# CAN_shield_rev0.net
KiCad netlist of a schematic drawn in EAGLE
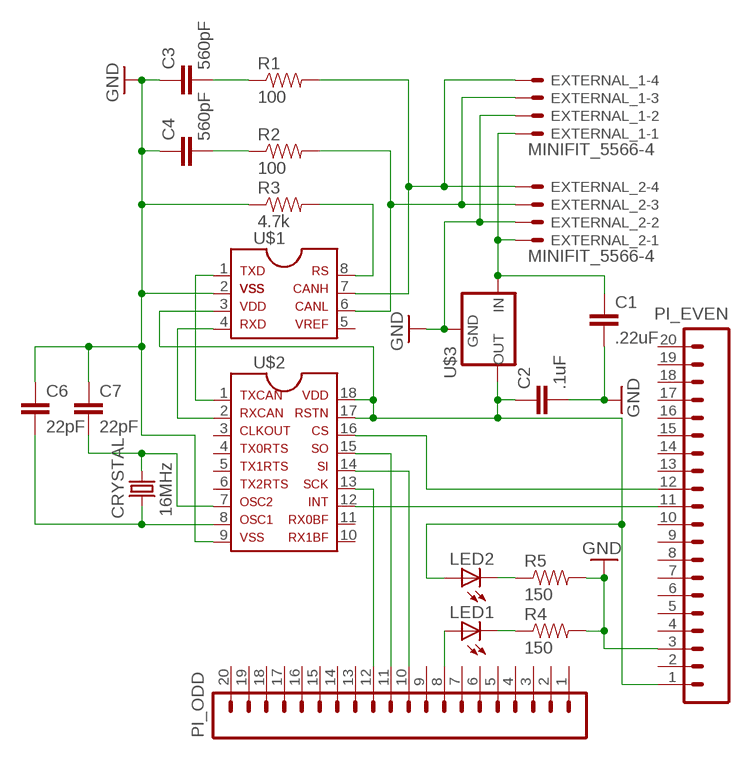
[diagram p0: schematic, sheet 1]

(export (version "E")
  (design (tool "Eeschema 10.0.6"))
  (components
    (comp (ref "C1")
      (value ".22uF")
      (footprint "eagle-import:0805")
      (libsource (lib "eagle-import") (part "CAP0805"))
    )
    (comp (ref "C2")
      (value ".1uF")
      (footprint "eagle-import:0805")
      (libsource (lib "eagle-import") (part "CAP0805"))
    )
    (comp (ref "C3")
      (value "560pF")
      (footprint "eagle-import:0805")
      (libsource (lib "eagle-import") (part "CAP0805"))
    )
    (comp (ref "C4")
      (value "560pF")
      (footprint "eagle-import:0805")
      (libsource (lib "eagle-import") (part "CAP0805"))
    )
    (comp (ref "C6")
      (value "22pF")
      (footprint "eagle-import:0805")
      (libsource (lib "eagle-import") (part "CAP0805"))
    )
    (comp (ref "C7")
      (value "22pF")
      (footprint "eagle-import:0805")
      (libsource (lib "eagle-import") (part "CAP0805"))
    )
    (comp (ref "CRYSTAL")
      (value "16MHz")
      (footprint "eagle-import:HC49UP")
      (libsource (lib "eagle-import") (part "CRYSTALSMD"))
    )
    (comp (ref "EXTERNAL_1")
      (value "MINIFIT_5566-4")
      (footprint "eagle-import:MINIFIT_5566-4")
      (libsource (lib "eagle-import") (part "MINIFIT_5566-4"))
    )
    (comp (ref "EXTERNAL_2")
      (value "MINIFIT_5566-4")
      (footprint "eagle-import:MINIFIT_5566-4")
      (libsource (lib "eagle-import") (part "MINIFIT_5566-4"))
    )
    (comp (ref "LED1")
      (value "LED-0805")
      (footprint "eagle-import:LED-805")
      (libsource (lib "eagle-import") (part "LED-0805"))
    )
    (comp (ref "LED2")
      (value "LED-0805")
      (footprint "eagle-import:LED-805")
      (libsource (lib "eagle-import") (part "LED-0805"))
    )
    (comp (ref "PI_EVEN")
      (value "M20")
      (footprint "eagle-import:1X20")
      (libsource (lib "eagle-import") (part "M20"))
    )
    (comp (ref "PI_ODD")
      (value "M20")
      (footprint "eagle-import:1X20")
      (libsource (lib "eagle-import") (part "M20"))
    )
    (comp (ref "R1")
      (value "100")
      (footprint "eagle-import:0805")
      (libsource (lib "eagle-import") (part "RESISTOR0805-RES"))
    )
    (comp (ref "R2")
      (value "100")
      (footprint "eagle-import:0805")
      (libsource (lib "eagle-import") (part "RESISTOR0805-RES"))
    )
    (comp (ref "R3")
      (value "4.7k")
      (footprint "eagle-import:0805")
      (libsource (lib "eagle-import") (part "RESISTOR0805-RES"))
    )
    (comp (ref "R4")
      (value "150")
      (footprint "eagle-import:0805")
      (libsource (lib "eagle-import") (part "RESISTOR0805-RES"))
    )
    (comp (ref "R5")
      (value "150")
      (footprint "eagle-import:0805")
      (libsource (lib "eagle-import") (part "RESISTOR0805-RES"))
    )
    (comp (ref "U$1")
      (value "MCP2551")
      (footprint "eagle-import:SOIC-08")
      (libsource (lib "eagle-import") (part "MCP2551"))
    )
    (comp (ref "U$2")
      (value "MCP2515SMD")
      (footprint "eagle-import:SOIC-18W")
      (libsource (lib "eagle-import") (part "MCP2515SMD"))
    )
    (comp (ref "U$3")
      (value "5V_REGULATOR_LM340-NLM340MPX-5.0/NOPB")
      (footprint "eagle-import:SOT223")
      (libsource (lib "eagle-import") (part "5V_REGULATOR_LM340-NLM340MPX-5.0/NOPB"))
    )
  )
  (nets
    (net (code "1") (name "GND") (class "Default")
      (node (ref "C1") (pin "2") (pinfunction "2_2") (pintype "passive"))
      (node (ref "C2") (pin "2") (pinfunction "2_2") (pintype "passive"))
      (node (ref "C3") (pin "1") (pinfunction "1_1") (pintype "passive"))
      (node (ref "C4") (pin "1") (pinfunction "1_1") (pintype "passive"))
      (node (ref "C6") (pin "1") (pinfunction "1_1") (pintype "passive"))
      (node (ref "C7") (pin "1") (pinfunction "1_1") (pintype "passive"))
      (node (ref "EXTERNAL_1") (pin "2") (pinfunction "S_2") (pintype "passive"))
      (node (ref "EXTERNAL_2") (pin "2") (pinfunction "S_2") (pintype "passive"))
      (node (ref "PI_EVEN") (pin "3") (pinfunction "3_3") (pintype "passive"))
      (node (ref "R3") (pin "1") (pinfunction "1_1") (pintype "passive"))
      (node (ref "R4") (pin "2") (pinfunction "2_2") (pintype "passive"))
      (node (ref "R5") (pin "2") (pinfunction "2_2") (pintype "passive"))
      (node (ref "U$1") (pin "2") (pinfunction "2_2") (pintype "passive"))
      (node (ref "U$2") (pin "9") (pinfunction "9_9") (pintype "passive"))
      (node (ref "U$3") (pin "2") (pinfunction "GND_2") (pintype "input"))
      (node (ref "U$3") (pin "4") (pinfunction "GND_4") (pintype "input"))
    )
    (net (code "2") (name "Net-(C3-Pad2)") (class "Default")
      (node (ref "C3") (pin "2") (pinfunction "2_2") (pintype "passive"))
      (node (ref "R1") (pin "1") (pinfunction "1_1") (pintype "passive"))
    )
    (net (code "3") (name "Net-(C4-Pad2)") (class "Default")
      (node (ref "C4") (pin "2") (pinfunction "2_2") (pintype "passive"))
      (node (ref "R2") (pin "1") (pinfunction "1_1") (pintype "passive"))
    )
    (net (code "4") (name "Net-(C6-Pad2)") (class "Default")
      (node (ref "C6") (pin "2") (pinfunction "2_2") (pintype "passive"))
      (node (ref "CRYSTAL") (pin "2") (pinfunction "2_2") (pintype "passive"))
      (node (ref "U$2") (pin "8") (pinfunction "8_8") (pintype "passive"))
    )
    (net (code "5") (name "Net-(C7-Pad2)") (class "Default")
      (node (ref "C7") (pin "2") (pinfunction "2_2") (pintype "passive"))
      (node (ref "CRYSTAL") (pin "1") (pinfunction "1_1") (pintype "passive"))
      (node (ref "U$2") (pin "7") (pinfunction "7_7") (pintype "passive"))
    )
    (net (code "6") (name "Net-(EXTERNAL_1A-S)") (class "Default")
      (node (ref "C1") (pin "1") (pinfunction "1_1") (pintype "passive"))
      (node (ref "EXTERNAL_1") (pin "1") (pinfunction "S_1") (pintype "passive"))
      (node (ref "EXTERNAL_2") (pin "1") (pinfunction "S_1") (pintype "passive"))
      (node (ref "U$3") (pin "1") (pinfunction "IN_1") (pintype "input"))
    )
    (net (code "7") (name "Net-(EXTERNAL_1C-S)") (class "Default")
      (node (ref "EXTERNAL_1") (pin "3") (pinfunction "S_3") (pintype "passive"))
      (node (ref "EXTERNAL_2") (pin "3") (pinfunction "S_3") (pintype "passive"))
      (node (ref "R2") (pin "2") (pinfunction "2_2") (pintype "passive"))
      (node (ref "U$1") (pin "6") (pinfunction "6_6") (pintype "passive"))
    )
    (net (code "8") (name "Net-(EXTERNAL_1D-S)") (class "Default")
      (node (ref "EXTERNAL_1") (pin "4") (pinfunction "S_4") (pintype "passive"))
      (node (ref "EXTERNAL_2") (pin "4") (pinfunction "S_4") (pintype "passive"))
      (node (ref "R1") (pin "2") (pinfunction "2_2") (pintype "passive"))
      (node (ref "U$1") (pin "7") (pinfunction "7_7") (pintype "passive"))
    )
    (net (code "9") (name "Net-(LED1-PadA)") (class "Default")
      (node (ref "LED1") (pin "A") (pinfunction "A_A") (pintype "passive"))
      (node (ref "PI_ODD") (pin "8") (pinfunction "8_8") (pintype "passive"))
    )
    (net (code "10") (name "Net-(LED1-PadC)") (class "Default")
      (node (ref "LED1") (pin "C") (pinfunction "C_C") (pintype "passive"))
      (node (ref "R4") (pin "1") (pinfunction "1_1") (pintype "passive"))
    )
    (net (code "11") (name "Net-(LED2-PadC)") (class "Default")
      (node (ref "LED2") (pin "C") (pinfunction "C_C") (pintype "passive"))
      (node (ref "R5") (pin "1") (pinfunction "1_1") (pintype "passive"))
    )
    (net (code "12") (name "Net-(PI_EVEN-Pad11)") (class "Default")
      (node (ref "PI_EVEN") (pin "11") (pinfunction "11_11") (pintype "passive"))
      (node (ref "U$2") (pin "12") (pinfunction "12_12") (pintype "passive"))
    )
    (net (code "13") (name "Net-(PI_EVEN-Pad12)") (class "Default")
      (node (ref "PI_EVEN") (pin "12") (pinfunction "12_12") (pintype "passive"))
      (node (ref "U$2") (pin "16") (pinfunction "16_16") (pintype "passive"))
    )
    (net (code "14") (name "Net-(PI_ODD-Pad10)") (class "Default")
      (node (ref "PI_ODD") (pin "10") (pinfunction "10_10") (pintype "passive"))
      (node (ref "U$2") (pin "14") (pinfunction "14_14") (pintype "passive"))
    )
    (net (code "15") (name "Net-(PI_ODD-Pad11)") (class "Default")
      (node (ref "PI_ODD") (pin "11") (pinfunction "11_11") (pintype "passive"))
      (node (ref "U$2") (pin "15") (pinfunction "15_15") (pintype "passive"))
    )
    (net (code "16") (name "Net-(PI_ODD-Pad12)") (class "Default")
      (node (ref "PI_ODD") (pin "12") (pinfunction "12_12") (pintype "passive"))
      (node (ref "U$2") (pin "13") (pinfunction "13_13") (pintype "passive"))
    )
    (net (code "17") (name "Net-(R3-Pad2)") (class "Default")
      (node (ref "R3") (pin "2") (pinfunction "2_2") (pintype "passive"))
      (node (ref "U$1") (pin "8") (pinfunction "8_8") (pintype "passive"))
    )
    (net (code "18") (name "Net-(U$1-Pad1)") (class "Default")
      (node (ref "U$1") (pin "1") (pinfunction "1_1") (pintype "passive"))
      (node (ref "U$2") (pin "1") (pinfunction "1_1") (pintype "passive"))
    )
    (net (code "19") (name "Net-(U$1-Pad4)") (class "Default")
      (node (ref "U$1") (pin "4") (pinfunction "4_4") (pintype "passive"))
      (node (ref "U$2") (pin "2") (pinfunction "2_2") (pintype "passive"))
    )
    (net (code "20") (name "Net-(U$3-OUT)") (class "Default")
      (node (ref "C2") (pin "1") (pinfunction "1_1") (pintype "passive"))
      (node (ref "LED2") (pin "A") (pinfunction "A_A") (pintype "passive"))
      (node (ref "PI_EVEN") (pin "1") (pinfunction "1_1") (pintype "passive"))
      (node (ref "U$1") (pin "3") (pinfunction "3_3") (pintype "passive"))
      (node (ref "U$2") (pin "17") (pinfunction "17_17") (pintype "passive"))
      (node (ref "U$2") (pin "18") (pinfunction "18_18") (pintype "passive"))
      (node (ref "U$3") (pin "3") (pinfunction "OUT_3") (pintype "output"))
    )
    (net (code "21") (name "unconnected-(PI_EVEN-Pad2)") (class "Default")
      (node (ref "PI_EVEN") (pin "2") (pinfunction "2_2") (pintype "passive"))
    )
    (net (code "22") (name "unconnected-(PI_EVEN-Pad4)") (class "Default")
      (node (ref "PI_EVEN") (pin "4") (pinfunction "4_4") (pintype "passive"))
    )
    (net (code "23") (name "unconnected-(PI_EVEN-Pad5)") (class "Default")
      (node (ref "PI_EVEN") (pin "5") (pinfunction "5_5") (pintype "passive"))
    )
    (net (code "24") (name "unconnected-(PI_EVEN-Pad6)") (class "Default")
      (node (ref "PI_EVEN") (pin "6") (pinfunction "6_6") (pintype "passive"))
    )
    (net (code "25") (name "unconnected-(PI_EVEN-Pad7)") (class "Default")
      (node (ref "PI_EVEN") (pin "7") (pinfunction "7_7") (pintype "passive"))
    )
    (net (code "26") (name "unconnected-(PI_EVEN-Pad8)") (class "Default")
      (node (ref "PI_EVEN") (pin "8") (pinfunction "8_8") (pintype "passive"))
    )
    (net (code "27") (name "unconnected-(PI_EVEN-Pad9)") (class "Default")
      (node (ref "PI_EVEN") (pin "9") (pinfunction "9_9") (pintype "passive"))
    )
    (net (code "28") (name "unconnected-(PI_EVEN-Pad10)") (class "Default")
      (node (ref "PI_EVEN") (pin "10") (pinfunction "10_10") (pintype "passive"))
    )
    (net (code "29") (name "unconnected-(PI_EVEN-Pad13)") (class "Default")
      (node (ref "PI_EVEN") (pin "13") (pinfunction "13_13") (pintype "passive"))
    )
    (net (code "30") (name "unconnected-(PI_EVEN-Pad14)") (class "Default")
      (node (ref "PI_EVEN") (pin "14") (pinfunction "14_14") (pintype "passive"))
    )
    (net (code "31") (name "unconnected-(PI_EVEN-Pad15)") (class "Default")
      (node (ref "PI_EVEN") (pin "15") (pinfunction "15_15") (pintype "passive"))
    )
    (net (code "32") (name "unconnected-(PI_EVEN-Pad16)") (class "Default")
      (node (ref "PI_EVEN") (pin "16") (pinfunction "16_16") (pintype "passive"))
    )
    (net (code "33") (name "unconnected-(PI_EVEN-Pad17)") (class "Default")
      (node (ref "PI_EVEN") (pin "17") (pinfunction "17_17") (pintype "passive"))
    )
    (net (code "34") (name "unconnected-(PI_EVEN-Pad18)") (class "Default")
      (node (ref "PI_EVEN") (pin "18") (pinfunction "18_18") (pintype "passive"))
    )
    (net (code "35") (name "unconnected-(PI_EVEN-Pad19)") (class "Default")
      (node (ref "PI_EVEN") (pin "19") (pinfunction "19_19") (pintype "passive"))
    )
    (net (code "36") (name "unconnected-(PI_EVEN-Pad20)") (class "Default")
      (node (ref "PI_EVEN") (pin "20") (pinfunction "20_20") (pintype "passive"))
    )
    (net (code "37") (name "unconnected-(PI_ODD-Pad1)") (class "Default")
      (node (ref "PI_ODD") (pin "1") (pinfunction "1_1") (pintype "passive"))
    )
    (net (code "38") (name "unconnected-(PI_ODD-Pad2)") (class "Default")
      (node (ref "PI_ODD") (pin "2") (pinfunction "2_2") (pintype "passive"))
    )
    (net (code "39") (name "unconnected-(PI_ODD-Pad3)") (class "Default")
      (node (ref "PI_ODD") (pin "3") (pinfunction "3_3") (pintype "passive"))
    )
    (net (code "40") (name "unconnected-(PI_ODD-Pad4)") (class "Default")
      (node (ref "PI_ODD") (pin "4") (pinfunction "4_4") (pintype "passive"))
    )
    (net (code "41") (name "unconnected-(PI_ODD-Pad5)") (class "Default")
      (node (ref "PI_ODD") (pin "5") (pinfunction "5_5") (pintype "passive"))
    )
    (net (code "42") (name "unconnected-(PI_ODD-Pad6)") (class "Default")
      (node (ref "PI_ODD") (pin "6") (pinfunction "6_6") (pintype "passive"))
    )
    (net (code "43") (name "unconnected-(PI_ODD-Pad7)") (class "Default")
      (node (ref "PI_ODD") (pin "7") (pinfunction "7_7") (pintype "passive"))
    )
    (net (code "44") (name "unconnected-(PI_ODD-Pad9)") (class "Default")
      (node (ref "PI_ODD") (pin "9") (pinfunction "9_9") (pintype "passive"))
    )
    (net (code "45") (name "unconnected-(PI_ODD-Pad13)") (class "Default")
      (node (ref "PI_ODD") (pin "13") (pinfunction "13_13") (pintype "passive"))
    )
    (net (code "46") (name "unconnected-(PI_ODD-Pad14)") (class "Default")
      (node (ref "PI_ODD") (pin "14") (pinfunction "14_14") (pintype "passive"))
    )
    (net (code "47") (name "unconnected-(PI_ODD-Pad15)") (class "Default")
      (node (ref "PI_ODD") (pin "15") (pinfunction "15_15") (pintype "passive"))
    )
    (net (code "48") (name "unconnected-(PI_ODD-Pad16)") (class "Default")
      (node (ref "PI_ODD") (pin "16") (pinfunction "16_16") (pintype "passive"))
    )
    (net (code "49") (name "unconnected-(PI_ODD-Pad17)") (class "Default")
      (node (ref "PI_ODD") (pin "17") (pinfunction "17_17") (pintype "passive"))
    )
    (net (code "50") (name "unconnected-(PI_ODD-Pad18)") (class "Default")
      (node (ref "PI_ODD") (pin "18") (pinfunction "18_18") (pintype "passive"))
    )
    (net (code "51") (name "unconnected-(PI_ODD-Pad19)") (class "Default")
      (node (ref "PI_ODD") (pin "19") (pinfunction "19_19") (pintype "passive"))
    )
    (net (code "52") (name "unconnected-(PI_ODD-Pad20)") (class "Default")
      (node (ref "PI_ODD") (pin "20") (pinfunction "20_20") (pintype "passive"))
    )
    (net (code "53") (name "unconnected-(U$1-Pad5)") (class "Default")
      (node (ref "U$1") (pin "5") (pinfunction "5_5") (pintype "passive"))
    )
    (net (code "54") (name "unconnected-(U$2-Pad3)") (class "Default")
      (node (ref "U$2") (pin "3") (pinfunction "3_3") (pintype "passive"))
    )
    (net (code "55") (name "unconnected-(U$2-Pad4)") (class "Default")
      (node (ref "U$2") (pin "4") (pinfunction "4_4") (pintype "passive"))
    )
    (net (code "56") (name "unconnected-(U$2-Pad5)") (class "Default")
      (node (ref "U$2") (pin "5") (pinfunction "5_5") (pintype "passive"))
    )
    (net (code "57") (name "unconnected-(U$2-Pad6)") (class "Default")
      (node (ref "U$2") (pin "6") (pinfunction "6_6") (pintype "passive"))
    )
    (net (code "58") (name "unconnected-(U$2-Pad10)") (class "Default")
      (node (ref "U$2") (pin "10") (pinfunction "10_10") (pintype "passive"))
    )
    (net (code "59") (name "unconnected-(U$2-Pad11)") (class "Default")
      (node (ref "U$2") (pin "11") (pinfunction "11_11") (pintype "passive"))
    )
  )
)
